# arducard.net
KiCad netlist of a schematic drawn in EAGLE
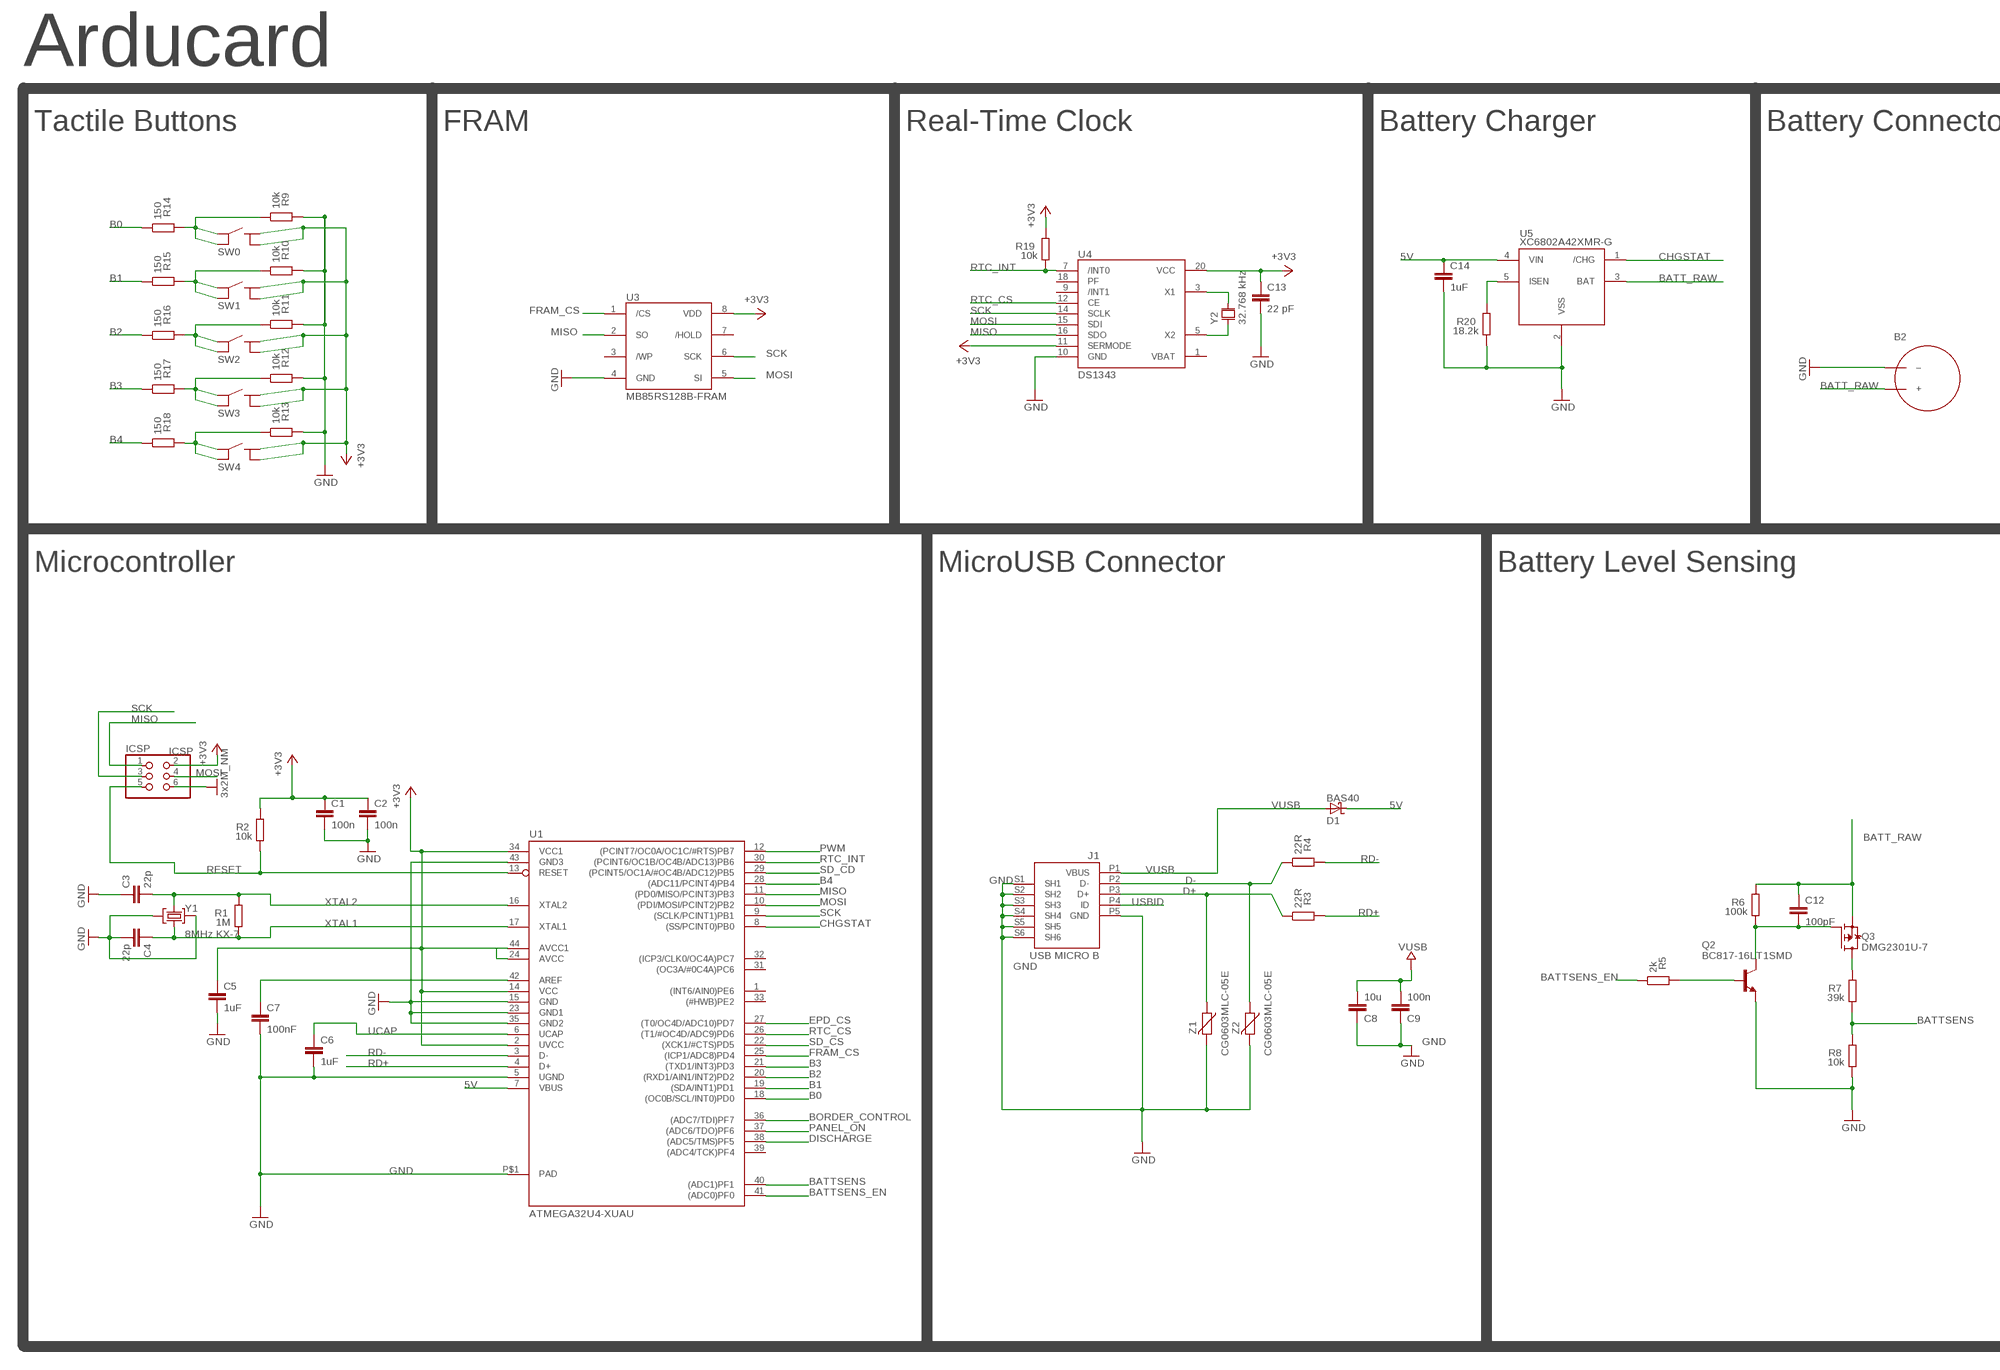
[diagram p0: schematic, sheet 1, part 1 of 2]
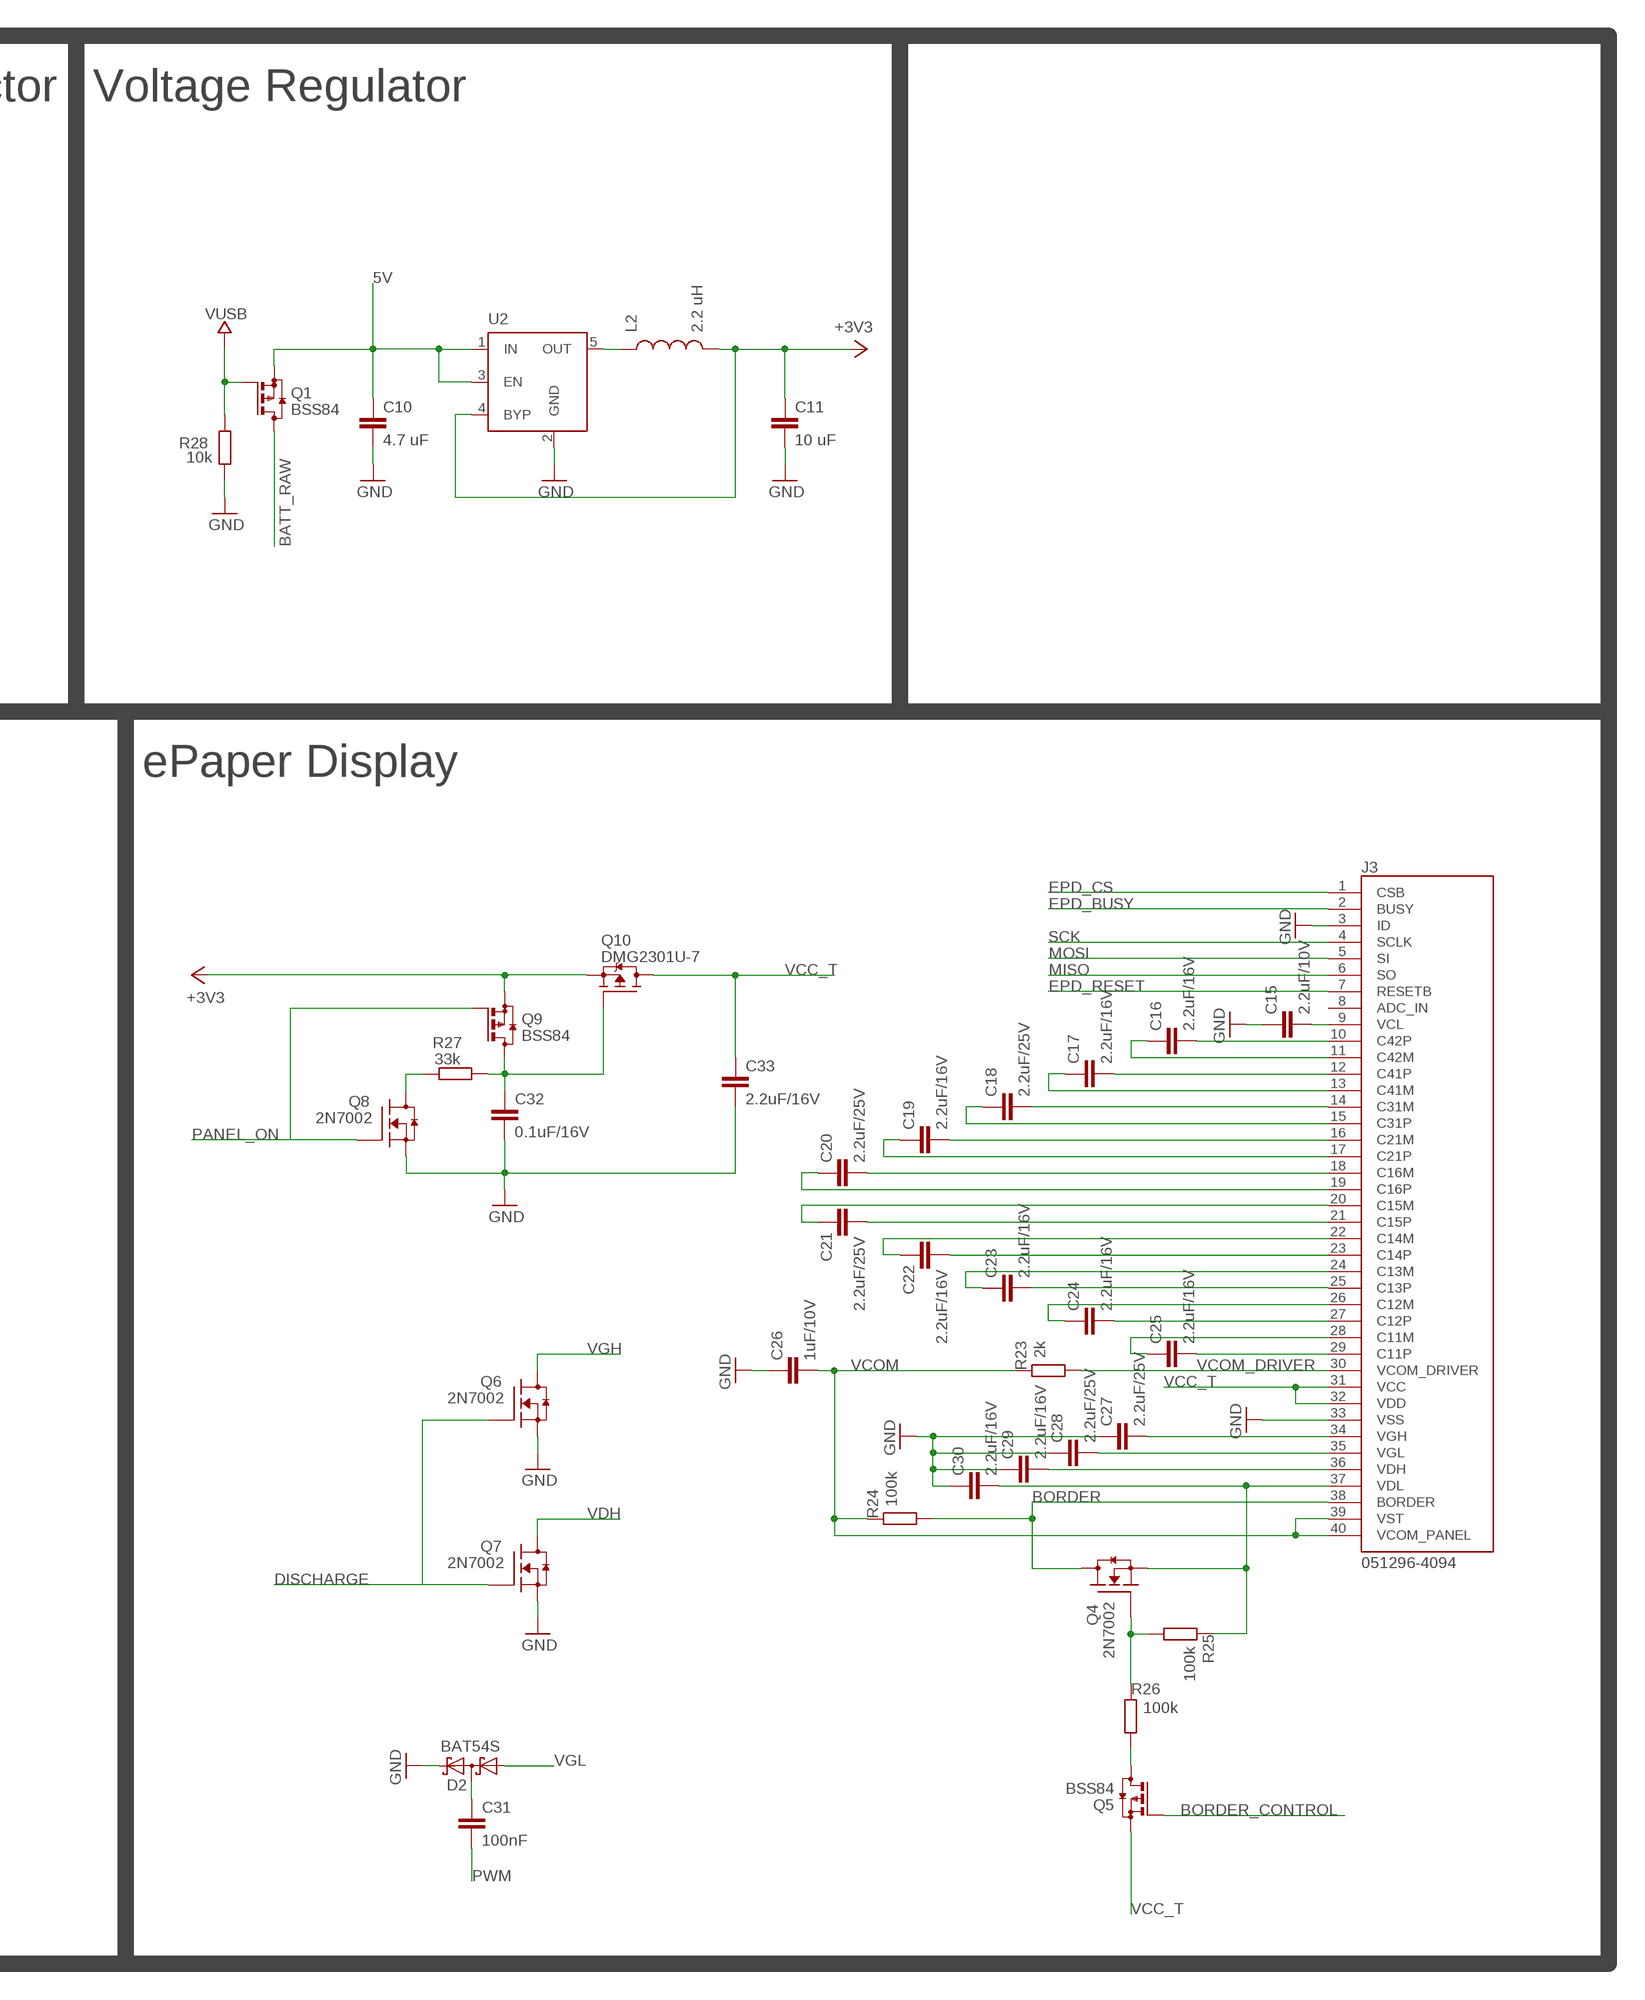
[diagram p1: schematic, sheet 1, part 2 of 2]

(export (version "E")
  (design (tool "Eeschema 10.0.6"))
  (components
    (comp (ref "B2")
      (value "LIR2016")
      (footprint "eagle-import:BK-5067")
      (libsource (lib "eagle-import") (part "LIR2016"))
    )
    (comp (ref "C1")
      (value "100n")
      (footprint "eagle-import:C0603-ROUND")
      (libsource (lib "eagle-import") (part "C-EUC0603"))
    )
    (comp (ref "C2")
      (value "100n")
      (footprint "eagle-import:C0603-ROUND")
      (libsource (lib "eagle-import") (part "C-EUC0603"))
    )
    (comp (ref "C3")
      (value "22p")
      (footprint "eagle-import:C0603-ROUND")
      (libsource (lib "eagle-import") (part "C-EUC0603"))
    )
    (comp (ref "C4")
      (value "22p")
      (footprint "eagle-import:C0603-ROUND")
      (libsource (lib "eagle-import") (part "C-EUC0603"))
    )
    (comp (ref "C5")
      (value "1uF")
      (footprint "eagle-import:C0603-ROUND")
      (libsource (lib "eagle-import") (part "C-EUC0603"))
    )
    (comp (ref "C6")
      (value "1uF")
      (footprint "eagle-import:C0603-ROUND")
      (libsource (lib "eagle-import") (part "C-EUC0603"))
    )
    (comp (ref "C7")
      (value "100nF")
      (footprint "eagle-import:C0603-ROUND")
      (libsource (lib "eagle-import") (part "C-EUC0603"))
    )
    (comp (ref "C8")
      (value "10u")
      (footprint "eagle-import:C0603-ROUND")
      (libsource (lib "eagle-import") (part "C-EUC0603"))
    )
    (comp (ref "C9")
      (value "100n")
      (footprint "eagle-import:C0603-ROUND")
      (libsource (lib "eagle-import") (part "C-EUC0603"))
    )
    (comp (ref "C10")
      (value "4.7 uF")
      (footprint "eagle-import:C0603-ROUND")
      (libsource (lib "eagle-import") (part "C-EUC0603"))
    )
    (comp (ref "C11")
      (value "10 uF")
      (footprint "eagle-import:C0603-ROUND")
      (libsource (lib "eagle-import") (part "C-EUC0603"))
    )
    (comp (ref "C12")
      (value "100pF")
      (footprint "eagle-import:C0603-ROUND")
      (libsource (lib "eagle-import") (part "C-EUC0603"))
    )
    (comp (ref "C13")
      (value "22 pF")
      (footprint "eagle-import:C0603-ROUND")
      (libsource (lib "eagle-import") (part "C-EUC0603"))
    )
    (comp (ref "C14")
      (value "1uF")
      (footprint "eagle-import:C0603-ROUND")
      (libsource (lib "eagle-import") (part "C-EUC0603"))
    )
    (comp (ref "C15")
      (value "2.2uF/10V")
      (footprint "eagle-import:C0603-ROUND")
      (libsource (lib "eagle-import") (part "C-EUC0603"))
    )
    (comp (ref "C16")
      (value "2.2uF/16V")
      (footprint "eagle-import:C0603-ROUND")
      (libsource (lib "eagle-import") (part "C-EUC0603"))
    )
    (comp (ref "C17")
      (value "2.2uF/16V")
      (footprint "eagle-import:C0603-ROUND")
      (libsource (lib "eagle-import") (part "C-EUC0603"))
    )
    (comp (ref "C18")
      (value "2.2uF/25V")
      (footprint "eagle-import:C0603-ROUND")
      (libsource (lib "eagle-import") (part "C-EUC0603"))
    )
    (comp (ref "C19")
      (value "2.2uF/16V")
      (footprint "eagle-import:C0603-ROUND")
      (libsource (lib "eagle-import") (part "C-EUC0603"))
    )
    (comp (ref "C20")
      (value "2.2uF/25V")
      (footprint "eagle-import:C0603-ROUND")
      (libsource (lib "eagle-import") (part "C-EUC0603"))
    )
    (comp (ref "C21")
      (value "2.2uF/25V")
      (footprint "eagle-import:C0603-ROUND")
      (libsource (lib "eagle-import") (part "C-EUC0603"))
    )
    (comp (ref "C22")
      (value "2.2uF/16V")
      (footprint "eagle-import:C0603-ROUND")
      (libsource (lib "eagle-import") (part "C-EUC0603"))
    )
    (comp (ref "C23")
      (value "2.2uF/16V")
      (footprint "eagle-import:C0603-ROUND")
      (libsource (lib "eagle-import") (part "C-EUC0603"))
    )
    (comp (ref "C24")
      (value "2.2uF/16V")
      (footprint "eagle-import:C0603-ROUND")
      (libsource (lib "eagle-import") (part "C-EUC0603"))
    )
    (comp (ref "C25")
      (value "2.2uF/16V")
      (footprint "eagle-import:C0603-ROUND")
      (libsource (lib "eagle-import") (part "C-EUC0603"))
    )
    (comp (ref "C26")
      (value "1uF/10V")
      (footprint "eagle-import:C0603-ROUND")
      (libsource (lib "eagle-import") (part "C-EUC0603"))
    )
    (comp (ref "C27")
      (value "2.2uF/25V")
      (footprint "eagle-import:C0603-ROUND")
      (libsource (lib "eagle-import") (part "C-EUC0603"))
    )
    (comp (ref "C28")
      (value "2.2uF/25V")
      (footprint "eagle-import:C0603-ROUND")
      (libsource (lib "eagle-import") (part "C-EUC0603"))
    )
    (comp (ref "C29")
      (value "2.2uF/16V")
      (footprint "eagle-import:C0603-ROUND")
      (libsource (lib "eagle-import") (part "C-EUC0603"))
    )
    (comp (ref "C30")
      (value "2.2uF/16V")
      (footprint "eagle-import:C0603-ROUND")
      (libsource (lib "eagle-import") (part "C-EUC0603"))
    )
    (comp (ref "C31")
      (value "100nF")
      (footprint "eagle-import:C0603-ROUND")
      (libsource (lib "eagle-import") (part "C-EUC0603"))
    )
    (comp (ref "C32")
      (value "0.1uF/16V")
      (footprint "eagle-import:C0603-ROUND")
      (libsource (lib "eagle-import") (part "C-EUC0603"))
    )
    (comp (ref "C33")
      (value "2.2uF/16V")
      (footprint "eagle-import:C0603-ROUND")
      (libsource (lib "eagle-import") (part "C-EUC0603"))
    )
    (comp (ref "D1")
      (value "BAS40")
      (footprint "eagle-import:SOT23")
      (libsource (lib "eagle-import") (part "BAS40"))
    )
    (comp (ref "D2")
      (value "BAT54S")
      (footprint "eagle-import:SOT23")
      (libsource (lib "eagle-import") (part "BAT54S"))
    )
    (comp (ref "ICSP")
      (value "ICSP")
      (footprint "eagle-import:2X03")
      (libsource (lib "eagle-import") (part "PINHD-2X3"))
    )
    (comp (ref "J1")
      (value "USB MICRO B")
      (footprint "eagle-import:CON2_USB_MICRO_B_AT")
      (libsource (lib "eagle-import") (part "MYCON2_USB-MINI-B"))
    )
    (comp (ref "J3")
      (value "051296-4094")
      (footprint "eagle-import:051296-4094")
      (libsource (lib "eagle-import") (part "051296-4094"))
    )
    (comp (ref "L2")
      (value "2.2 uH")
      (footprint "eagle-import:0603")
      (libsource (lib "eagle-import") (part "INDUCTOR30OHM,1.8A"))
    )
    (comp (ref "Q1")
      (value "BSS84")
      (footprint "eagle-import:SOT23")
      (libsource (lib "eagle-import") (part "BSS84"))
    )
    (comp (ref "Q2")
      (value "BC817-16LT1SMD")
      (footprint "eagle-import:SOT23-BEC")
      (libsource (lib "eagle-import") (part "BC817SMD-16LT1"))
    )
    (comp (ref "Q3")
      (value "DMG2301U-7")
      (footprint "eagle-import:SOT23")
      (libsource (lib "eagle-import") (part "DMG2301U-7"))
    )
    (comp (ref "Q4")
      (value "2N7002")
      (footprint "eagle-import:SOT-23")
      (libsource (lib "eagle-import") (part "2N7002"))
    )
    (comp (ref "Q5")
      (value "BSS84")
      (footprint "eagle-import:SOT23")
      (libsource (lib "eagle-import") (part "BSS84"))
    )
    (comp (ref "Q6")
      (value "2N7002")
      (footprint "eagle-import:SOT-23")
      (libsource (lib "eagle-import") (part "2N7002"))
    )
    (comp (ref "Q7")
      (value "2N7002")
      (footprint "eagle-import:SOT-23")
      (libsource (lib "eagle-import") (part "2N7002"))
    )
    (comp (ref "Q8")
      (value "2N7002")
      (footprint "eagle-import:SOT-23")
      (libsource (lib "eagle-import") (part "2N7002"))
    )
    (comp (ref "Q9")
      (value "BSS84")
      (footprint "eagle-import:SOT23")
      (libsource (lib "eagle-import") (part "BSS84"))
    )
    (comp (ref "Q10")
      (value "DMG2301U-7")
      (footprint "eagle-import:SOT23")
      (libsource (lib "eagle-import") (part "DMG2301U-7"))
    )
    (comp (ref "R1")
      (value "1M")
      (footprint "eagle-import:R0603-ROUND")
      (libsource (lib "eagle-import") (part "R-EU_R0603"))
    )
    (comp (ref "R2")
      (value "10k")
      (footprint "eagle-import:R0603-ROUND")
      (libsource (lib "eagle-import") (part "R-EU_R0603"))
    )
    (comp (ref "R3")
      (value "22R")
      (footprint "eagle-import:R0603-ROUND")
      (libsource (lib "eagle-import") (part "R-EU_R0603"))
    )
    (comp (ref "R4")
      (value "22R")
      (footprint "eagle-import:R0603-ROUND")
      (libsource (lib "eagle-import") (part "R-EU_R0603"))
    )
    (comp (ref "R5")
      (value "2k")
      (footprint "eagle-import:R0603-ROUND")
      (libsource (lib "eagle-import") (part "R-EU_R0603"))
    )
    (comp (ref "R6")
      (value "100k")
      (footprint "eagle-import:R0603-ROUND")
      (libsource (lib "eagle-import") (part "R-EU_R0603"))
    )
    (comp (ref "R7")
      (value "39k")
      (footprint "eagle-import:R0603-ROUND")
      (libsource (lib "eagle-import") (part "R-EU_R0603"))
    )
    (comp (ref "R8")
      (value "10k")
      (footprint "eagle-import:R0603-ROUND")
      (libsource (lib "eagle-import") (part "R-EU_R0603"))
    )
    (comp (ref "R9")
      (value "10k")
      (footprint "eagle-import:R0603-ROUND")
      (libsource (lib "eagle-import") (part "R-EU_R0603"))
    )
    (comp (ref "R10")
      (value "10k")
      (footprint "eagle-import:R0603-ROUND")
      (libsource (lib "eagle-import") (part "R-EU_R0603"))
    )
    (comp (ref "R11")
      (value "10k")
      (footprint "eagle-import:R0603-ROUND")
      (libsource (lib "eagle-import") (part "R-EU_R0603"))
    )
    (comp (ref "R12")
      (value "10k")
      (footprint "eagle-import:R0603-ROUND")
      (libsource (lib "eagle-import") (part "R-EU_R0603"))
    )
    (comp (ref "R13")
      (value "10k")
      (footprint "eagle-import:R0603-ROUND")
      (libsource (lib "eagle-import") (part "R-EU_R0603"))
    )
    (comp (ref "R14")
      (value "150")
      (footprint "eagle-import:R0603-ROUND")
      (libsource (lib "eagle-import") (part "R-EU_R0603"))
    )
    (comp (ref "R15")
      (value "150")
      (footprint "eagle-import:R0603-ROUND")
      (libsource (lib "eagle-import") (part "R-EU_R0603"))
    )
    (comp (ref "R16")
      (value "150")
      (footprint "eagle-import:R0603-ROUND")
      (libsource (lib "eagle-import") (part "R-EU_R0603"))
    )
    (comp (ref "R17")
      (value "150")
      (footprint "eagle-import:R0603-ROUND")
      (libsource (lib "eagle-import") (part "R-EU_R0603"))
    )
    (comp (ref "R18")
      (value "150")
      (footprint "eagle-import:R0603-ROUND")
      (libsource (lib "eagle-import") (part "R-EU_R0603"))
    )
    (comp (ref "R19")
      (value "10k")
      (footprint "eagle-import:R0603-ROUND")
      (libsource (lib "eagle-import") (part "R-EU_R0603"))
    )
    (comp (ref "R20")
      (value "18.2k")
      (footprint "eagle-import:R0603-ROUND")
      (libsource (lib "eagle-import") (part "R-EU_R0603"))
    )
    (comp (ref "R23")
      (value "2k")
      (footprint "eagle-import:R0603-ROUND")
      (libsource (lib "eagle-import") (part "R-EU_R0603"))
    )
    (comp (ref "R24")
      (value "100k")
      (footprint "eagle-import:R0603-ROUND")
      (libsource (lib "eagle-import") (part "R-EU_R0603"))
    )
    (comp (ref "R25")
      (value "100k")
      (footprint "eagle-import:R0603-ROUND")
      (libsource (lib "eagle-import") (part "R-EU_R0603"))
    )
    (comp (ref "R26")
      (value "100k")
      (footprint "eagle-import:R0603-ROUND")
      (libsource (lib "eagle-import") (part "R-EU_R0603"))
    )
    (comp (ref "R27")
      (value "33k")
      (footprint "eagle-import:R0603-ROUND")
      (libsource (lib "eagle-import") (part "R-EU_R0603"))
    )
    (comp (ref "R28")
      (value "10k")
      (footprint "eagle-import:R0603-ROUND")
      (libsource (lib "eagle-import") (part "R-EU_R0603"))
    )
    (comp (ref "SW0")
      (value "EVQ-PUA")
      (footprint "eagle-import:SMD-TACT-SWITCH")
      (libsource (lib "eagle-import") (part "EVQ-PUA"))
    )
    (comp (ref "SW1")
      (value "EVQ-PUA")
      (footprint "eagle-import:SMD-TACT-SWITCH")
      (libsource (lib "eagle-import") (part "EVQ-PUA"))
    )
    (comp (ref "SW2")
      (value "EVQ-PUA")
      (footprint "eagle-import:SMD-TACT-SWITCH")
      (libsource (lib "eagle-import") (part "EVQ-PUA"))
    )
    (comp (ref "SW3")
      (value "EVQ-PUA")
      (footprint "eagle-import:SMD-TACT-SWITCH")
      (libsource (lib "eagle-import") (part "EVQ-PUA"))
    )
    (comp (ref "SW4")
      (value "EVQ-PUA")
      (footprint "eagle-import:SMD-TACT-SWITCH")
      (libsource (lib "eagle-import") (part "EVQ-PUA"))
    )
    (comp (ref "U1")
      (value "ATMEGA32U4-XUAU")
      (footprint "eagle-import:TQFP44-PAD")
      (libsource (lib "eagle-import") (part "ATMEGA32U4-XUAU"))
    )
    (comp (ref "U2")
      (value "MIC5219XX")
      (footprint "eagle-import:SOT23-5")
      (libsource (lib "eagle-import") (part "MIC5219XX"))
    )
    (comp (ref "U3")
      (value "MB85RS128B-FRAM")
      (footprint "eagle-import:SO-08")
      (libsource (lib "eagle-import") (part "MB85RS128B-FRAM"))
    )
    (comp (ref "U4")
      (value "DS1343")
      (footprint "eagle-import:TSSOP20")
      (libsource (lib "eagle-import") (part "DS1343"))
    )
    (comp (ref "U5")
      (value "XC6802A42XMR-G")
      (footprint "eagle-import:SOT23-5L")
      (libsource (lib "eagle-import") (part "XC6802A42XMR-G"))
    )
    (comp (ref "Y1")
      (value "8MHz KX-7")
      (footprint "eagle-import:CRYSTAL-3.2-2.5")
      (libsource (lib "eagle-import") (part "CRYSTAL-3.2-2.5"))
    )
    (comp (ref "Y2")
      (value "32.768 kHz")
      (footprint "eagle-import:SSP-T7-F")
      (libsource (lib "eagle-import") (part "SSP-T7-F"))
    )
    (comp (ref "Z1")
      (value "CG0603MLC-05E")
      (footprint "eagle-import:CT_CN0603")
      (libsource (lib "eagle-import") (part "VARISTORCN0603"))
    )
    (comp (ref "Z2")
      (value "CG0603MLC-05E")
      (footprint "eagle-import:CT_CN0603")
      (libsource (lib "eagle-import") (part "VARISTORCN0603"))
    )
  )
  (nets
    (net (code "1") (name "+3V3") (class "Default")
      (node (ref "C1") (pin "1") (pinfunction "1_1") (pintype "passive"))
      (node (ref "C11") (pin "1") (pinfunction "1_1") (pintype "passive"))
      (node (ref "C13") (pin "1") (pinfunction "1_1") (pintype "passive"))
      (node (ref "C2") (pin "1") (pinfunction "1_1") (pintype "passive"))
      (node (ref "C5") (pin "1") (pinfunction "1_1") (pintype "passive"))
      (node (ref "ICSP") (pin "2") (pinfunction "2_2") (pintype "passive"))
      (node (ref "L2") (pin "2") (pinfunction "2_2") (pintype "passive"))
      (node (ref "Q10") (pin "2") (pinfunction "S_2") (pintype "passive"))
      (node (ref "Q9") (pin "2") (pinfunction "S_2") (pintype "passive"))
      (node (ref "R19") (pin "2") (pinfunction "2_2") (pintype "passive"))
      (node (ref "R2") (pin "2") (pinfunction "2_2") (pintype "passive"))
      (node (ref "SW0") (pin "2") (pinfunction "2_2") (pintype "bidirectional"))
      (node (ref "SW0") (pin "4") (pinfunction "4_4") (pintype "bidirectional"))
      (node (ref "SW1") (pin "2") (pinfunction "2_2") (pintype "bidirectional"))
      (node (ref "SW1") (pin "4") (pinfunction "4_4") (pintype "bidirectional"))
      (node (ref "SW2") (pin "2") (pinfunction "2_2") (pintype "bidirectional"))
      (node (ref "SW2") (pin "4") (pinfunction "4_4") (pintype "bidirectional"))
      (node (ref "SW3") (pin "2") (pinfunction "2_2") (pintype "bidirectional"))
      (node (ref "SW3") (pin "4") (pinfunction "4_4") (pintype "bidirectional"))
      (node (ref "SW4") (pin "2") (pinfunction "2_2") (pintype "bidirectional"))
      (node (ref "SW4") (pin "4") (pinfunction "4_4") (pintype "bidirectional"))
      (node (ref "U1") (pin "14") (pinfunction "VCC_14") (pintype "power_in"))
      (node (ref "U1") (pin "2") (pinfunction "UVCC_2") (pintype "power_in"))
      (node (ref "U1") (pin "24") (pinfunction "AVCC_24") (pintype "power_in"))
      (node (ref "U1") (pin "34") (pinfunction "VCC1_34") (pintype "power_in"))
      (node (ref "U1") (pin "44") (pinfunction "AVCC1_44") (pintype "power_in"))
      (node (ref "U2") (pin "4") (pinfunction "BYP_4") (pintype "passive"))
      (node (ref "U3") (pin "8") (pinfunction "VDD_8") (pintype "power_in"))
      (node (ref "U4") (pin "11") (pinfunction "SERMODE_11") (pintype "bidirectional"))
      (node (ref "U4") (pin "20") (pinfunction "VCC_20") (pintype "power_in"))
    )
    (net (code "2") (name "/5V") (class "Default")
      (node (ref "C10") (pin "1") (pinfunction "1_1") (pintype "passive"))
      (node (ref "C14") (pin "1") (pinfunction "1_1") (pintype "passive"))
      (node (ref "D1") (pin "3") (pinfunction "C_3") (pintype "passive"))
      (node (ref "Q1") (pin "2") (pinfunction "S_2") (pintype "passive"))
      (node (ref "U1") (pin "7") (pinfunction "VBUS_7") (pintype "input"))
      (node (ref "U2") (pin "1") (pinfunction "IN_1") (pintype "input"))
      (node (ref "U2") (pin "3") (pinfunction "EN_3") (pintype "input"))
      (node (ref "U5") (pin "4") (pinfunction "VIN_4") (pintype "power_in"))
    )
    (net (code "3") (name "/B0") (class "Default")
      (node (ref "R14") (pin "1") (pinfunction "1_1") (pintype "passive"))
      (node (ref "U1") (pin "18") (pinfunction "(OC0B/SCL/INT0)PD0_18") (pintype "bidirectional"))
    )
    (net (code "4") (name "/B1") (class "Default")
      (node (ref "R15") (pin "1") (pinfunction "1_1") (pintype "passive"))
      (node (ref "U1") (pin "19") (pinfunction "(SDA/INT1)PD1_19") (pintype "bidirectional"))
    )
    (net (code "5") (name "/B2") (class "Default")
      (node (ref "R16") (pin "1") (pinfunction "1_1") (pintype "passive"))
      (node (ref "U1") (pin "20") (pinfunction "(RXD1/AIN1/INT2)PD2_20") (pintype "bidirectional"))
    )
    (net (code "6") (name "/B3") (class "Default")
      (node (ref "R17") (pin "1") (pinfunction "1_1") (pintype "passive"))
      (node (ref "U1") (pin "21") (pinfunction "(TXD1/INT3)PD3_21") (pintype "bidirectional"))
    )
    (net (code "7") (name "/B4") (class "Default")
      (node (ref "R18") (pin "1") (pinfunction "1_1") (pintype "passive"))
      (node (ref "U1") (pin "28") (pinfunction "(ADC11/PCINT4)PB4_28") (pintype "bidirectional"))
    )
    (net (code "8") (name "/BATTSENS") (class "Default")
      (node (ref "R7") (pin "1") (pinfunction "1_1") (pintype "passive"))
      (node (ref "R8") (pin "2") (pinfunction "2_2") (pintype "passive"))
      (node (ref "U1") (pin "40") (pinfunction "(ADC1)PF1_40") (pintype "bidirectional"))
    )
    (net (code "9") (name "/BATTSENS_EN") (class "Default")
      (node (ref "R5") (pin "1") (pinfunction "1_1") (pintype "passive"))
      (node (ref "U1") (pin "41") (pinfunction "(ADC0)PF0_41") (pintype "bidirectional"))
    )
    (net (code "10") (name "/BATT_RAW") (class "Default")
      (node (ref "B2") (pin "POS1") (pinfunction "+_POS1") (pintype "bidirectional"))
      (node (ref "B2") (pin "POS2") (pinfunction "+_POS2") (pintype "bidirectional"))
      (node (ref "C12") (pin "1") (pinfunction "1_1") (pintype "passive"))
      (node (ref "Q1") (pin "3") (pinfunction "D_3") (pintype "passive"))
      (node (ref "Q3") (pin "2") (pinfunction "S_2") (pintype "passive"))
      (node (ref "R6") (pin "2") (pinfunction "2_2") (pintype "passive"))
      (node (ref "U5") (pin "3") (pinfunction "BAT_3") (pintype "power_in"))
    )
    (net (code "11") (name "/BORDER") (class "Default")
      (node (ref "J3") (pin "38") (pinfunction "BORDER_38") (pintype "bidirectional"))
      (node (ref "Q4") (pin "3") (pinfunction "D_3") (pintype "passive"))
      (node (ref "R24") (pin "2") (pinfunction "2_2") (pintype "passive"))
    )
    (net (code "12") (name "/BORDER_CONTROL") (class "Default")
      (node (ref "Q5") (pin "1") (pinfunction "G_1") (pintype "passive"))
      (node (ref "U1") (pin "36") (pinfunction "(ADC7/TDI)PF7_36") (pintype "bidirectional"))
    )
    (net (code "13") (name "/CHGSTAT") (class "Default")
      (node (ref "U1") (pin "8") (pinfunction "(SS/PCINT0)PB0_8") (pintype "bidirectional"))
      (node (ref "U5") (pin "1") (pinfunction "/CHG_1") (pintype "bidirectional"))
    )
    (net (code "14") (name "/D+") (class "Default")
      (node (ref "J1") (pin "P3") (pinfunction "D+_P3") (pintype "bidirectional"))
      (node (ref "R3") (pin "1") (pinfunction "1_1") (pintype "passive"))
      (node (ref "Z1") (pin "1") (pinfunction "1_1") (pintype "passive"))
    )
    (net (code "15") (name "/D-") (class "Default")
      (node (ref "J1") (pin "P2") (pinfunction "D-_P2") (pintype "bidirectional"))
      (node (ref "R4") (pin "1") (pinfunction "1_1") (pintype "passive"))
      (node (ref "Z2") (pin "1") (pinfunction "1_1") (pintype "passive"))
    )
    (net (code "16") (name "/DISCHARGE") (class "Default")
      (node (ref "Q6") (pin "1") (pinfunction "G_1") (pintype "passive"))
      (node (ref "Q7") (pin "1") (pinfunction "G_1") (pintype "passive"))
      (node (ref "U1") (pin "38") (pinfunction "(ADC5/TMS)PF5_38") (pintype "bidirectional"))
    )
    (net (code "17") (name "/EPD_BUSY") (class "Default")
      (node (ref "J3") (pin "2") (pinfunction "BUSY_2") (pintype "bidirectional"))
    )
    (net (code "18") (name "/EPD_CS") (class "Default")
      (node (ref "J3") (pin "1") (pinfunction "CSB_1") (pintype "bidirectional"))
      (node (ref "U1") (pin "27") (pinfunction "(T0/OC4D/ADC10)PD7_27") (pintype "bidirectional"))
    )
    (net (code "19") (name "/EPD_RESET") (class "Default")
      (node (ref "J3") (pin "7") (pinfunction "RESETB_7") (pintype "bidirectional"))
    )
    (net (code "20") (name "/FRAM_CS") (class "Default")
      (node (ref "U1") (pin "25") (pinfunction "(ICP1/ADC8)PD4_25") (pintype "bidirectional"))
      (node (ref "U3") (pin "1") (pinfunction "/CS_1") (pintype "bidirectional"))
    )
    (net (code "21") (name "/MISO") (class "Default")
      (node (ref "ICSP") (pin "1") (pinfunction "1_1") (pintype "passive"))
      (node (ref "J3") (pin "6") (pinfunction "SO_6") (pintype "bidirectional"))
      (node (ref "U1") (pin "11") (pinfunction "(PD0/MISO/PCINT3)PB3_11") (pintype "bidirectional"))
      (node (ref "U3") (pin "2") (pinfunction "SO_2") (pintype "bidirectional"))
      (node (ref "U4") (pin "16") (pinfunction "SDO_16") (pintype "bidirectional"))
    )
    (net (code "22") (name "/MOSI") (class "Default")
      (node (ref "ICSP") (pin "4") (pinfunction "4_4") (pintype "passive"))
      (node (ref "J3") (pin "5") (pinfunction "SI_5") (pintype "bidirectional"))
      (node (ref "U1") (pin "10") (pinfunction "(PDI/MOSI/PCINT2)PB2_10") (pintype "bidirectional"))
      (node (ref "U3") (pin "5") (pinfunction "SI_5") (pintype "bidirectional"))
      (node (ref "U4") (pin "15") (pinfunction "SDI_15") (pintype "bidirectional"))
    )
    (net (code "23") (name "/PANEL_ON") (class "Default")
      (node (ref "Q8") (pin "1") (pinfunction "G_1") (pintype "passive"))
      (node (ref "Q9") (pin "1") (pinfunction "G_1") (pintype "passive"))
      (node (ref "U1") (pin "37") (pinfunction "(ADC6/TDO)PF6_37") (pintype "bidirectional"))
    )
    (net (code "24") (name "/PWM") (class "Default")
      (node (ref "C31") (pin "2") (pinfunction "2_2") (pintype "passive"))
      (node (ref "U1") (pin "12") (pinfunction "(PCINT7/OC0A/OC1C/#RTS)PB7_12") (pintype "bidirectional"))
    )
    (net (code "25") (name "/RD+") (class "Default")
      (node (ref "R3") (pin "2") (pinfunction "2_2") (pintype "passive"))
      (node (ref "U1") (pin "4") (pinfunction "D+_4") (pintype "bidirectional"))
    )
    (net (code "26") (name "/RD-") (class "Default")
      (node (ref "R4") (pin "2") (pinfunction "2_2") (pintype "passive"))
      (node (ref "U1") (pin "3") (pinfunction "D-_3") (pintype "bidirectional"))
    )
    (net (code "27") (name "/RESET") (class "Default")
      (node (ref "ICSP") (pin "5") (pinfunction "5_5") (pintype "passive"))
      (node (ref "R2") (pin "1") (pinfunction "1_1") (pintype "passive"))
      (node (ref "U1") (pin "13") (pinfunction "RESET_13") (pintype "input"))
    )
    (net (code "28") (name "/RTC_CS") (class "Default")
      (node (ref "U1") (pin "26") (pinfunction "(T1/#OC4D/ADC9)PD6_26") (pintype "bidirectional"))
      (node (ref "U4") (pin "12") (pinfunction "CE_12") (pintype "bidirectional"))
    )
    (net (code "29") (name "/RTC_INT") (class "Default")
      (node (ref "R19") (pin "1") (pinfunction "1_1") (pintype "passive"))
      (node (ref "U1") (pin "30") (pinfunction "(PCINT6/OC1B/OC4B/ADC13)PB6_30") (pintype "bidirectional"))
      (node (ref "U4") (pin "7") (pinfunction "/INT0_7") (pintype "bidirectional"))
    )
    (net (code "30") (name "/SCK") (class "Default")
      (node (ref "ICSP") (pin "3") (pinfunction "3_3") (pintype "passive"))
      (node (ref "J3") (pin "4") (pinfunction "SCLK_4") (pintype "bidirectional"))
      (node (ref "U1") (pin "9") (pinfunction "(SCLK/PCINT1)PB1_9") (pintype "bidirectional"))
      (node (ref "U3") (pin "6") (pinfunction "SCK_6") (pintype "bidirectional"))
      (node (ref "U4") (pin "14") (pinfunction "SCLK_14") (pintype "bidirectional"))
    )
    (net (code "31") (name "/SD_CD") (class "Default")
      (node (ref "U1") (pin "29") (pinfunction "(PCINT5/OC1A/#OC4B/ADC12)PB5_29") (pintype "bidirectional"))
    )
    (net (code "32") (name "/SD_CS") (class "Default")
      (node (ref "U1") (pin "22") (pinfunction "(XCK1/#CTS)PD5_22") (pintype "bidirectional"))
    )
    (net (code "33") (name "/UCAP") (class "Default")
      (node (ref "C6") (pin "1") (pinfunction "1_1") (pintype "passive"))
      (node (ref "U1") (pin "6") (pinfunction "UCAP_6") (pintype "passive"))
    )
    (net (code "34") (name "/USBID") (class "Default")
      (node (ref "J1") (pin "P4") (pinfunction "ID_P4") (pintype "bidirectional"))
    )
    (net (code "35") (name "/VCC_T") (class "Default")
      (node (ref "C33") (pin "1") (pinfunction "1_1") (pintype "passive"))
      (node (ref "J3") (pin "31") (pinfunction "VCC_31") (pintype "bidirectional"))
      (node (ref "J3") (pin "32") (pinfunction "VDD_32") (pintype "bidirectional"))
      (node (ref "Q10") (pin "3") (pinfunction "D_3") (pintype "passive"))
      (node (ref "Q5") (pin "2") (pinfunction "S_2") (pintype "passive"))
    )
    (net (code "36") (name "/VCOM") (class "Default")
      (node (ref "C26") (pin "2") (pinfunction "2_2") (pintype "passive"))
      (node (ref "J3") (pin "39") (pinfunction "VST_39") (pintype "bidirectional"))
      (node (ref "J3") (pin "40") (pinfunction "VCOM_PANEL_40") (pintype "bidirectional"))
      (node (ref "R23") (pin "1") (pinfunction "1_1") (pintype "passive"))
      (node (ref "R24") (pin "1") (pinfunction "1_1") (pintype "passive"))
    )
    (net (code "37") (name "/VCOM_DRIVER") (class "Default")
      (node (ref "J3") (pin "30") (pinfunction "VCOM_DRIVER_30") (pintype "bidirectional"))
      (node (ref "R23") (pin "2") (pinfunction "2_2") (pintype "passive"))
    )
    (net (code "38") (name "/VDH") (class "Default")
      (node (ref "C29") (pin "2") (pinfunction "2_2") (pintype "passive"))
      (node (ref "J3") (pin "36") (pinfunction "VDH_36") (pintype "bidirectional"))
      (node (ref "Q7") (pin "3") (pinfunction "D_3") (pintype "passive"))
    )
    (net (code "39") (name "/VGH") (class "Default")
      (node (ref "C27") (pin "2") (pinfunction "2_2") (pintype "passive"))
      (node (ref "J3") (pin "34") (pinfunction "VGH_34") (pintype "bidirectional"))
      (node (ref "Q6") (pin "3") (pinfunction "D_3") (pintype "passive"))
    )
    (net (code "40") (name "/VGL") (class "Default")
      (node (ref "C28") (pin "2") (pinfunction "2_2") (pintype "passive"))
      (node (ref "D2") (pin "1") (pinfunction "A1_1") (pintype "passive"))
      (node (ref "J3") (pin "35") (pinfunction "VGL_35") (pintype "bidirectional"))
    )
    (net (code "41") (name "/XTAL1") (class "Default")
      (node (ref "C4") (pin "1") (pinfunction "1_1") (pintype "passive"))
      (node (ref "R1") (pin "1") (pinfunction "1_1") (pintype "passive"))
      (node (ref "U1") (pin "17") (pinfunction "XTAL1_17") (pintype "bidirectional"))
      (node (ref "Y1") (pin "1") (pinfunction "C1_1") (pintype "passive"))
    )
    (net (code "42") (name "/XTAL2") (class "Default")
      (node (ref "C3") (pin "2") (pinfunction "2_2") (pintype "passive"))
      (node (ref "R1") (pin "2") (pinfunction "2_2") (pintype "passive"))
      (node (ref "U1") (pin "16") (pinfunction "XTAL2_16") (pintype "bidirectional"))
      (node (ref "Y1") (pin "3") (pinfunction "C2_3") (pintype "passive"))
    )
    (net (code "43") (name "3x2M_NM") (class "Default")
      (node (ref "B2") (pin "NEG") (pinfunction "–_NEG") (pintype "bidirectional"))
      (node (ref "C1") (pin "2") (pinfunction "2_2") (pintype "passive"))
      (node (ref "C10") (pin "2") (pinfunction "2_2") (pintype "passive"))
      (node (ref "C11") (pin "2") (pinfunction "2_2") (pintype "passive"))
      (node (ref "C13") (pin "2") (pinfunction "2_2") (pintype "passive"))
      (node (ref "C14") (pin "2") (pinfunction "2_2") (pintype "passive"))
      (node (ref "C15") (pin "1") (pinfunction "1_1") (pintype "passive"))
      (node (ref "C2") (pin "2") (pinfunction "2_2") (pintype "passive"))
      (node (ref "C26") (pin "1") (pinfunction "1_1") (pintype "passive"))
      (node (ref "C27") (pin "1") (pinfunction "1_1") (pintype "passive"))
      (node (ref "C28") (pin "1") (pinfunction "1_1") (pintype "passive"))
      (node (ref "C29") (pin "1") (pinfunction "1_1") (pintype "passive"))
      (node (ref "C3") (pin "1") (pinfunction "1_1") (pintype "passive"))
      (node (ref "C30") (pin "1") (pinfunction "1_1") (pintype "passive"))
      (node (ref "C32") (pin "2") (pinfunction "2_2") (pintype "passive"))
      (node (ref "C33") (pin "2") (pinfunction "2_2") (pintype "passive"))
      (node (ref "C4") (pin "2") (pinfunction "2_2") (pintype "passive"))
      (node (ref "C5") (pin "2") (pinfunction "2_2") (pintype "passive"))
      (node (ref "C6") (pin "2") (pinfunction "2_2") (pintype "passive"))
      (node (ref "C7") (pin "2") (pinfunction "2_2") (pintype "passive"))
      (node (ref "C8") (pin "1") (pinfunction "1_1") (pintype "passive"))
      (node (ref "C9") (pin "1") (pinfunction "1_1") (pintype "passive"))
      (node (ref "D2") (pin "2") (pinfunction "C2_2") (pintype "passive"))
      (node (ref "ICSP") (pin "6") (pinfunction "6_6") (pintype "passive"))
      (node (ref "J1") (pin "P5") (pinfunction "GND_P5") (pintype "passive"))
      (node (ref "J1") (pin "S1") (pinfunction "SH1_S1") (pintype "passive"))
      (node (ref "J1") (pin "S2") (pinfunction "SH2_S2") (pintype "passive"))
      (node (ref "J1") (pin "S3") (pinfunction "SH3_S3") (pintype "passive"))
      (node (ref "J1") (pin "S4") (pinfunction "SH4_S4") (pintype "passive"))
      (node (ref "J1") (pin "S5") (pinfunction "SH5_S5") (pintype "passive"))
      (node (ref "J1") (pin "S6") (pinfunction "SH6_S6") (pintype "passive"))
      (node (ref "J3") (pin "3") (pinfunction "ID_3") (pintype "bidirectional"))
      (node (ref "J3") (pin "33") (pinfunction "VSS_33") (pintype "bidirectional"))
      (node (ref "Q2") (pin "E") (pinfunction "E_E") (pintype "passive"))
      (node (ref "Q6") (pin "2") (pinfunction "S_2") (pintype "passive"))
      (node (ref "Q7") (pin "2") (pinfunction "S_2") (pintype "passive"))
      (node (ref "Q8") (pin "2") (pinfunction "S_2") (pintype "passive"))
      (node (ref "R10") (pin "2") (pinfunction "2_2") (pintype "passive"))
      (node (ref "R11") (pin "2") (pinfunction "2_2") (pintype "passive"))
      (node (ref "R12") (pin "2") (pinfunction "2_2") (pintype "passive"))
      (node (ref "R13") (pin "2") (pinfunction "2_2") (pintype "passive"))
      (node (ref "R20") (pin "1") (pinfunction "1_1") (pintype "passive"))
      (node (ref "R28") (pin "1") (pinfunction "1_1") (pintype "passive"))
      (node (ref "R8") (pin "1") (pinfunction "1_1") (pintype "passive"))
      (node (ref "R9") (pin "2") (pinfunction "2_2") (pintype "passive"))
      (node (ref "U1") (pin "15") (pinfunction "GND_15") (pintype "power_in"))
      (node (ref "U1") (pin "23") (pinfunction "GND1_23") (pintype "power_in"))
      (node (ref "U1") (pin "35") (pinfunction "GND2_35") (pintype "power_in"))
      (node (ref "U1") (pin "43") (pinfunction "GND3_43") (pintype "power_in"))
      (node (ref "U1") (pin "5") (pinfunction "UGND_5") (pintype "power_in"))
      (node (ref "U1") (pin "P$1") (pinfunction "PAD_P$1") (pintype "power_in"))
      (node (ref "U2") (pin "2") (pinfunction "GND_2") (pintype "power_in"))
      (node (ref "U3") (pin "4") (pinfunction "GND_4") (pintype "power_in"))
      (node (ref "U4") (pin "10") (pinfunction "GND_10") (pintype "power_in"))
      (node (ref "U5") (pin "2") (pinfunction "VSS_2") (pintype "power_in"))
      (node (ref "Y1") (pin "2") (pinfunction "GND_2") (pintype "passive"))
      (node (ref "Y1") (pin "4") (pinfunction "GND_4") (pintype "passive"))
      (node (ref "Z1") (pin "2") (pinfunction "2_2") (pintype "passive"))
      (node (ref "Z2") (pin "2") (pinfunction "2_2") (pintype "passive"))
    )
    (net (code "44") (name "Net-(D2-C1A2)") (class "Default")
      (node (ref "C31") (pin "1") (pinfunction "1_1") (pintype "passive"))
      (node (ref "D2") (pin "3") (pinfunction "C1A2_3") (pintype "passive"))
    )
    (net (code "45") (name "Net-(J3-C11M)") (class "Default")
      (node (ref "C25") (pin "1") (pinfunction "1_1") (pintype "passive"))
      (node (ref "J3") (pin "28") (pinfunction "C11M_28") (pintype "bidirectional"))
    )
    (net (code "46") (name "Net-(J3-C11P)") (class "Default")
      (node (ref "C25") (pin "2") (pinfunction "2_2") (pintype "passive"))
      (node (ref "J3") (pin "29") (pinfunction "C11P_29") (pintype "bidirectional"))
    )
    (net (code "47") (name "Net-(J3-C12M)") (class "Default")
      (node (ref "C24") (pin "1") (pinfunction "1_1") (pintype "passive"))
      (node (ref "J3") (pin "26") (pinfunction "C12M_26") (pintype "bidirectional"))
    )
    (net (code "48") (name "Net-(J3-C12P)") (class "Default")
      (node (ref "C24") (pin "2") (pinfunction "2_2") (pintype "passive"))
      (node (ref "J3") (pin "27") (pinfunction "C12P_27") (pintype "bidirectional"))
    )
    (net (code "49") (name "Net-(J3-C13M)") (class "Default")
      (node (ref "C23") (pin "1") (pinfunction "1_1") (pintype "passive"))
      (node (ref "J3") (pin "24") (pinfunction "C13M_24") (pintype "bidirectional"))
    )
    (net (code "50") (name "Net-(J3-C13P)") (class "Default")
      (node (ref "C23") (pin "2") (pinfunction "2_2") (pintype "passive"))
      (node (ref "J3") (pin "25") (pinfunction "C13P_25") (pintype "bidirectional"))
    )
    (net (code "51") (name "Net-(J3-C14M)") (class "Default")
      (node (ref "C22") (pin "1") (pinfunction "1_1") (pintype "passive"))
      (node (ref "J3") (pin "22") (pinfunction "C14M_22") (pintype "bidirectional"))
    )
    (net (code "52") (name "Net-(J3-C14P)") (class "Default")
      (node (ref "C22") (pin "2") (pinfunction "2_2") (pintype "passive"))
      (node (ref "J3") (pin "23") (pinfunction "C14P_23") (pintype "bidirectional"))
    )
    (net (code "53") (name "Net-(J3-C15M)") (class "Default")
      (node (ref "C21") (pin "1") (pinfunction "1_1") (pintype "passive"))
      (node (ref "J3") (pin "20") (pinfunction "C15M_20") (pintype "bidirectional"))
    )
    (net (code "54") (name "Net-(J3-C15P)") (class "Default")
      (node (ref "C21") (pin "2") (pinfunction "2_2") (pintype "passive"))
      (node (ref "J3") (pin "21") (pinfunction "C15P_21") (pintype "bidirectional"))
    )
    (net (code "55") (name "Net-(J3-C16M)") (class "Default")
      (node (ref "C20") (pin "2") (pinfunction "2_2") (pintype "passive"))
      (node (ref "J3") (pin "18") (pinfunction "C16M_18") (pintype "bidirectional"))
    )
    (net (code "56") (name "Net-(J3-C16P)") (class "Default")
      (node (ref "C20") (pin "1") (pinfunction "1_1") (pintype "passive"))
      (node (ref "J3") (pin "19") (pinfunction "C16P_19") (pintype "bidirectional"))
    )
    (net (code "57") (name "Net-(J3-C21M)") (class "Default")
      (node (ref "C19") (pin "2") (pinfunction "2_2") (pintype "passive"))
      (node (ref "J3") (pin "16") (pinfunction "C21M_16") (pintype "bidirectional"))
    )
    (net (code "58") (name "Net-(J3-C21P)") (class "Default")
      (node (ref "C19") (pin "1") (pinfunction "1_1") (pintype "passive"))
      (node (ref "J3") (pin "17") (pinfunction "C21P_17") (pintype "bidirectional"))
    )
    (net (code "59") (name "Net-(J3-C31M)") (class "Default")
      (node (ref "C18") (pin "2") (pinfunction "2_2") (pintype "passive"))
      (node (ref "J3") (pin "14") (pinfunction "C31M_14") (pintype "bidirectional"))
    )
    (net (code "60") (name "Net-(J3-C31P)") (class "Default")
      (node (ref "C18") (pin "1") (pinfunction "1_1") (pintype "passive"))
      (node (ref "J3") (pin "15") (pinfunction "C31P_15") (pintype "bidirectional"))
    )
    (net (code "61") (name "Net-(J3-C41M)") (class "Default")
      (node (ref "C17") (pin "1") (pinfunction "1_1") (pintype "passive"))
      (node (ref "J3") (pin "13") (pinfunction "C41M_13") (pintype "bidirectional"))
    )
    (net (code "62") (name "Net-(J3-C41P)") (class "Default")
      (node (ref "C17") (pin "2") (pinfunction "2_2") (pintype "passive"))
      (node (ref "J3") (pin "12") (pinfunction "C41P_12") (pintype "bidirectional"))
    )
    (net (code "63") (name "Net-(J3-C42M)") (class "Default")
      (node (ref "C16") (pin "1") (pinfunction "1_1") (pintype "passive"))
      (node (ref "J3") (pin "11") (pinfunction "C42M_11") (pintype "bidirectional"))
    )
    (net (code "64") (name "Net-(J3-C42P)") (class "Default")
      (node (ref "C16") (pin "2") (pinfunction "2_2") (pintype "passive"))
      (node (ref "J3") (pin "10") (pinfunction "C42P_10") (pintype "bidirectional"))
    )
    (net (code "65") (name "Net-(J3-VCL)") (class "Default")
      (node (ref "C15") (pin "2") (pinfunction "2_2") (pintype "passive"))
      (node (ref "J3") (pin "9") (pinfunction "VCL_9") (pintype "bidirectional"))
    )
    (net (code "66") (name "Net-(J3-VDL)") (class "Default")
      (node (ref "C30") (pin "2") (pinfunction "2_2") (pintype "passive"))
      (node (ref "J3") (pin "37") (pinfunction "VDL_37") (pintype "bidirectional"))
      (node (ref "Q4") (pin "2") (pinfunction "S_2") (pintype "passive"))
      (node (ref "R25") (pin "1") (pinfunction "1_1") (pintype "passive"))
    )
    (net (code "67") (name "Net-(Q2-PadB)") (class "Default")
      (node (ref "Q2") (pin "B") (pinfunction "B_B") (pintype "passive"))
      (node (ref "R5") (pin "2") (pinfunction "2_2") (pintype "passive"))
    )
    (net (code "68") (name "Net-(Q3-D)") (class "Default")
      (node (ref "Q3") (pin "3") (pinfunction "D_3") (pintype "passive"))
      (node (ref "R7") (pin "2") (pinfunction "2_2") (pintype "passive"))
    )
    (net (code "69") (name "Net-(Q3-G)") (class "Default")
      (node (ref "C12") (pin "2") (pinfunction "2_2") (pintype "passive"))
      (node (ref "Q2") (pin "C") (pinfunction "C_C") (pintype "passive"))
      (node (ref "Q3") (pin "1") (pinfunction "G_1") (pintype "passive"))
      (node (ref "R6") (pin "1") (pinfunction "1_1") (pintype "passive"))
    )
    (net (code "70") (name "Net-(Q4-G)") (class "Default")
      (node (ref "Q4") (pin "1") (pinfunction "G_1") (pintype "passive"))
      (node (ref "R25") (pin "2") (pinfunction "2_2") (pintype "passive"))
      (node (ref "R26") (pin "1") (pinfunction "1_1") (pintype "passive"))
    )
    (net (code "71") (name "Net-(Q5-D)") (class "Default")
      (node (ref "Q5") (pin "3") (pinfunction "D_3") (pintype "passive"))
      (node (ref "R26") (pin "2") (pinfunction "2_2") (pintype "passive"))
    )
    (net (code "72") (name "Net-(Q8-D)") (class "Default")
      (node (ref "Q8") (pin "3") (pinfunction "D_3") (pintype "passive"))
      (node (ref "R27") (pin "1") (pinfunction "1_1") (pintype "passive"))
    )
    (net (code "73") (name "Net-(Q10-G)") (class "Default")
      (node (ref "C32") (pin "1") (pinfunction "1_1") (pintype "passive"))
      (node (ref "Q10") (pin "1") (pinfunction "G_1") (pintype "passive"))
      (node (ref "Q9") (pin "3") (pinfunction "D_3") (pintype "passive"))
      (node (ref "R27") (pin "2") (pinfunction "2_2") (pintype "passive"))
    )
    (net (code "74") (name "Net-(R10-Pad1)") (class "Default")
      (node (ref "R10") (pin "1") (pinfunction "1_1") (pintype "passive"))
      (node (ref "R15") (pin "2") (pinfunction "2_2") (pintype "passive"))
      (node (ref "SW1") (pin "1") (pinfunction "1_1") (pintype "bidirectional"))
      (node (ref "SW1") (pin "3") (pinfunction "3_3") (pintype "bidirectional"))
    )
    (net (code "75") (name "Net-(R11-Pad1)") (class "Default")
      (node (ref "R11") (pin "1") (pinfunction "1_1") (pintype "passive"))
      (node (ref "R16") (pin "2") (pinfunction "2_2") (pintype "passive"))
      (node (ref "SW2") (pin "1") (pinfunction "1_1") (pintype "bidirectional"))
      (node (ref "SW2") (pin "3") (pinfunction "3_3") (pintype "bidirectional"))
    )
    (net (code "76") (name "Net-(R12-Pad1)") (class "Default")
      (node (ref "R12") (pin "1") (pinfunction "1_1") (pintype "passive"))
      (node (ref "R17") (pin "2") (pinfunction "2_2") (pintype "passive"))
      (node (ref "SW3") (pin "1") (pinfunction "1_1") (pintype "bidirectional"))
      (node (ref "SW3") (pin "3") (pinfunction "3_3") (pintype "bidirectional"))
    )
    (net (code "77") (name "Net-(R13-Pad1)") (class "Default")
      (node (ref "R13") (pin "1") (pinfunction "1_1") (pintype "passive"))
      (node (ref "R18") (pin "2") (pinfunction "2_2") (pintype "passive"))
      (node (ref "SW4") (pin "1") (pinfunction "1_1") (pintype "bidirectional"))
      (node (ref "SW4") (pin "3") (pinfunction "3_3") (pintype "bidirectional"))
    )
    (net (code "78") (name "Net-(R14-Pad2)") (class "Default")
      (node (ref "R14") (pin "2") (pinfunction "2_2") (pintype "passive"))
      (node (ref "R9") (pin "1") (pinfunction "1_1") (pintype "passive"))
      (node (ref "SW0") (pin "1") (pinfunction "1_1") (pintype "bidirectional"))
      (node (ref "SW0") (pin "3") (pinfunction "3_3") (pintype "bidirectional"))
    )
    (net (code "79") (name "Net-(U1-AREF)") (class "Default")
      (node (ref "C7") (pin "1") (pinfunction "1_1") (pintype "passive"))
      (node (ref "U1") (pin "42") (pinfunction "AREF_42") (pintype "power_in"))
    )
    (net (code "80") (name "Net-(U2-OUT)") (class "Default")
      (node (ref "L2") (pin "1") (pinfunction "1_1") (pintype "passive"))
      (node (ref "U2") (pin "5") (pinfunction "OUT_5") (pintype "output"))
    )
    (net (code "81") (name "Net-(U4-X1)") (class "Default")
      (node (ref "U4") (pin "3") (pinfunction "X1_3") (pintype "bidirectional"))
      (node (ref "Y2") (pin "P$4") (pinfunction "P$2_P$4") (pintype "passive"))
    )
    (net (code "82") (name "Net-(U4-X2)") (class "Default")
      (node (ref "U4") (pin "5") (pinfunction "X2_5") (pintype "bidirectional"))
      (node (ref "Y2") (pin "P$1") (pinfunction "P$1_P$1") (pintype "passive"))
    )
    (net (code "83") (name "Net-(U5-ISEN)") (class "Default")
      (node (ref "R20") (pin "2") (pinfunction "2_2") (pintype "passive"))
      (node (ref "U5") (pin "5") (pinfunction "ISEN_5") (pintype "bidirectional"))
    )
    (net (code "84") (name "VUSB") (class "Default")
      (node (ref "C8") (pin "2") (pinfunction "2_2") (pintype "passive"))
      (node (ref "C9") (pin "2") (pinfunction "2_2") (pintype "passive"))
      (node (ref "D1") (pin "1") (pinfunction "A_1") (pintype "passive"))
      (node (ref "J1") (pin "P1") (pinfunction "VBUS_P1") (pintype "power_in"))
      (node (ref "Q1") (pin "1") (pinfunction "G_1") (pintype "passive"))
      (node (ref "R28") (pin "2") (pinfunction "2_2") (pintype "passive"))
    )
    (net (code "85") (name "unconnected-(J3-ADC_IN-Pad8)") (class "Default")
      (node (ref "J3") (pin "8") (pinfunction "ADC_IN_8") (pintype "bidirectional"))
    )
    (net (code "86") (name "unconnected-(U1-(#HWB)PE2-Pad33)") (class "Default")
      (node (ref "U1") (pin "33") (pinfunction "(#HWB)PE2_33") (pintype "bidirectional"))
    )
    (net (code "87") (name "unconnected-(U1-(ADC4{slash}TCK)PF4-Pad39)") (class "Default")
      (node (ref "U1") (pin "39") (pinfunction "(ADC4/TCK)PF4_39") (pintype "bidirectional"))
    )
    (net (code "88") (name "unconnected-(U1-(ICP3{slash}CLK0{slash}OC4A)PC7-Pad32)") (class "Default")
      (node (ref "U1") (pin "32") (pinfunction "(ICP3/CLK0/OC4A)PC7_32") (pintype "bidirectional"))
    )
    (net (code "89") (name "unconnected-(U1-(INT6{slash}AIN0)PE6-Pad1)") (class "Default")
      (node (ref "U1") (pin "1") (pinfunction "(INT6/AIN0)PE6_1") (pintype "bidirectional"))
    )
    (net (code "90") (name "unconnected-(U1-(OC3A{slash}#0C4A)PC6-Pad31)") (class "Default")
      (node (ref "U1") (pin "31") (pinfunction "(OC3A/#0C4A)PC6_31") (pintype "bidirectional"))
    )
    (net (code "91") (name "unconnected-(U3-{slash}HOLD-Pad7)") (class "Default")
      (node (ref "U3") (pin "7") (pinfunction "/HOLD_7") (pintype "bidirectional"))
    )
    (net (code "92") (name "unconnected-(U3-{slash}WP-Pad3)") (class "Default")
      (node (ref "U3") (pin "3") (pinfunction "/WP_3") (pintype "bidirectional"))
    )
    (net (code "93") (name "unconnected-(U4-PF-Pad18)") (class "Default")
      (node (ref "U4") (pin "18") (pinfunction "PF_18") (pintype "bidirectional"))
    )
    (net (code "94") (name "unconnected-(U4-VBAT-Pad1)") (class "Default")
      (node (ref "U4") (pin "1") (pinfunction "VBAT_1") (pintype "bidirectional"))
    )
    (net (code "95") (name "unconnected-(U4-{slash}INT1-Pad9)") (class "Default")
      (node (ref "U4") (pin "9") (pinfunction "/INT1_9") (pintype "bidirectional"))
    )
  )
)
